# FPGA_POWER.net
KiCad netlist of a schematic drawn in Altium Designer
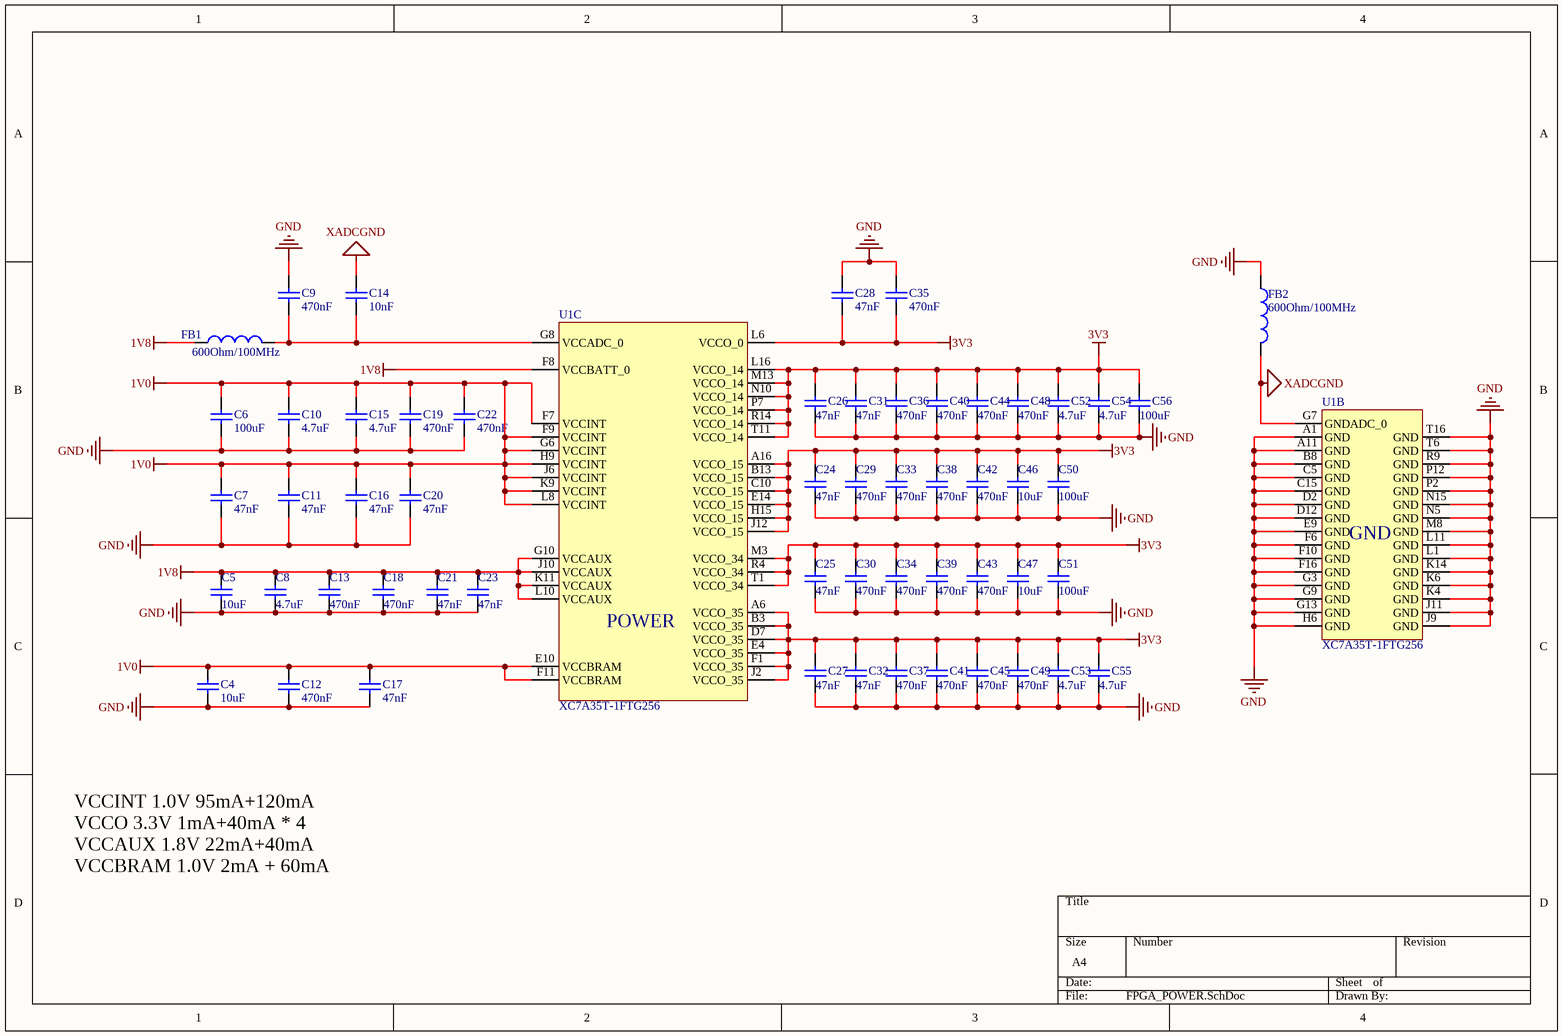
[diagram p0: FPGA_POWER.SchDoc]

(export (version "E")
  (design (tool "Eeschema 10.0.6"))
  (components
    (comp (ref "C4")
      (value "10uF")
      (footprint "0402")
      (description "贴片电容")
      (fields (field (name "Comment") "Cap") (field (name "PUBLISHER") "Altium Limited"))
      (libsource (lib "Sparks") (part "Cap"))
    )
    (comp (ref "C5")
      (value "10uF")
      (footprint "0402")
      (description "贴片电容")
      (fields (field (name "Comment") "Cap") (field (name "PUBLISHER") "Altium Limited"))
      (libsource (lib "Sparks") (part "Cap"))
    )
    (comp (ref "C6")
      (value "100uF")
      (footprint "1206")
      (description "贴片电容")
      (fields (field (name "Comment") "Cap") (field (name "PUBLISHER") "Altium Limited"))
      (libsource (lib "Sparks") (part "Cap"))
    )
    (comp (ref "C7")
      (value "47nF")
      (footprint "0402")
      (description "贴片电容")
      (fields (field (name "Comment") "Cap") (field (name "PUBLISHER") "Altium Limited"))
      (libsource (lib "Sparks") (part "Cap"))
    )
    (comp (ref "C8")
      (value "4.7uF")
      (footprint "0402")
      (description "贴片电容")
      (fields (field (name "Comment") "Cap") (field (name "PUBLISHER") "Altium Limited"))
      (libsource (lib "Sparks") (part "Cap"))
    )
    (comp (ref "C9")
      (value "470nF")
      (footprint "0402")
      (description "贴片电容")
      (fields (field (name "Comment") "Cap") (field (name "PUBLISHER") "Altium Limited"))
      (libsource (lib "Sparks") (part "Cap"))
    )
    (comp (ref "C10")
      (value "4.7uF")
      (footprint "0402")
      (description "贴片电容")
      (fields (field (name "Comment") "Cap") (field (name "PUBLISHER") "Altium Limited"))
      (libsource (lib "Sparks") (part "Cap"))
    )
    (comp (ref "C11")
      (value "47nF")
      (footprint "0402")
      (description "贴片电容")
      (fields (field (name "Comment") "Cap") (field (name "PUBLISHER") "Altium Limited"))
      (libsource (lib "Sparks") (part "Cap"))
    )
    (comp (ref "C12")
      (value "470nF")
      (footprint "0402")
      (description "贴片电容")
      (fields (field (name "Comment") "Cap") (field (name "PUBLISHER") "Altium Limited"))
      (libsource (lib "Sparks") (part "Cap"))
    )
    (comp (ref "C13")
      (value "470nF")
      (footprint "0402")
      (description "贴片电容")
      (fields (field (name "Comment") "Cap") (field (name "PUBLISHER") "Altium Limited"))
      (libsource (lib "Sparks") (part "Cap"))
    )
    (comp (ref "C14")
      (value "10nF")
      (footprint "0402")
      (description "贴片电容")
      (fields (field (name "Comment") "Cap") (field (name "PUBLISHER") "Altium Limited"))
      (libsource (lib "Sparks") (part "Cap"))
    )
    (comp (ref "C15")
      (value "4.7uF")
      (footprint "0402")
      (description "贴片电容")
      (fields (field (name "Comment") "Cap") (field (name "PUBLISHER") "Altium Limited"))
      (libsource (lib "Sparks") (part "Cap"))
    )
    (comp (ref "C16")
      (value "47nF")
      (footprint "0402")
      (description "贴片电容")
      (fields (field (name "Comment") "Cap") (field (name "PUBLISHER") "Altium Limited"))
      (libsource (lib "Sparks") (part "Cap"))
    )
    (comp (ref "C17")
      (value "47nF")
      (footprint "0402")
      (description "贴片电容")
      (fields (field (name "Comment") "Cap") (field (name "PUBLISHER") "Altium Limited"))
      (libsource (lib "Sparks") (part "Cap"))
    )
    (comp (ref "C18")
      (value "470nF")
      (footprint "0402")
      (description "贴片电容")
      (fields (field (name "Comment") "Cap") (field (name "PUBLISHER") "Altium Limited"))
      (libsource (lib "Sparks") (part "Cap"))
    )
    (comp (ref "C19")
      (value "470nF")
      (footprint "0402")
      (description "贴片电容")
      (fields (field (name "Comment") "Cap") (field (name "PUBLISHER") "Altium Limited"))
      (libsource (lib "Sparks") (part "Cap"))
    )
    (comp (ref "C20")
      (value "47nF")
      (footprint "0402")
      (description "贴片电容")
      (fields (field (name "Comment") "Cap") (field (name "PUBLISHER") "Altium Limited"))
      (libsource (lib "Sparks") (part "Cap"))
    )
    (comp (ref "C21")
      (value "47nF")
      (footprint "0402")
      (description "贴片电容")
      (fields (field (name "Comment") "Cap") (field (name "PUBLISHER") "Altium Limited"))
      (libsource (lib "Sparks") (part "Cap"))
    )
    (comp (ref "C22")
      (value "470nF")
      (footprint "0402")
      (description "贴片电容")
      (fields (field (name "Comment") "Cap") (field (name "PUBLISHER") "Altium Limited"))
      (libsource (lib "Sparks") (part "Cap"))
    )
    (comp (ref "C23")
      (value "47nF")
      (footprint "0402")
      (description "贴片电容")
      (fields (field (name "Comment") "Cap") (field (name "PUBLISHER") "Altium Limited"))
      (libsource (lib "Sparks") (part "Cap"))
    )
    (comp (ref "C24")
      (value "47nF")
      (footprint "0402")
      (description "贴片电容")
      (fields (field (name "Comment") "Cap") (field (name "PUBLISHER") "Altium Limited"))
      (libsource (lib "Sparks") (part "Cap"))
    )
    (comp (ref "C25")
      (value "47nF")
      (footprint "0402")
      (description "贴片电容")
      (fields (field (name "Comment") "Cap") (field (name "PUBLISHER") "Altium Limited"))
      (libsource (lib "Sparks") (part "Cap"))
    )
    (comp (ref "C26")
      (value "47nF")
      (footprint "0402")
      (description "贴片电容")
      (fields (field (name "Comment") "Cap") (field (name "PUBLISHER") "Altium Limited"))
      (libsource (lib "Sparks") (part "Cap"))
    )
    (comp (ref "C27")
      (value "47nF")
      (footprint "0402")
      (description "贴片电容")
      (fields (field (name "Comment") "Cap") (field (name "PUBLISHER") "Altium Limited"))
      (libsource (lib "Sparks") (part "Cap"))
    )
    (comp (ref "C28")
      (value "47nF")
      (footprint "0402")
      (description "贴片电容")
      (fields (field (name "Comment") "Cap") (field (name "PUBLISHER") "Altium Limited"))
      (libsource (lib "Sparks") (part "Cap"))
    )
    (comp (ref "C29")
      (value "470nF")
      (footprint "0402")
      (description "贴片电容")
      (fields (field (name "Comment") "Cap") (field (name "PUBLISHER") "Altium Limited"))
      (libsource (lib "Sparks") (part "Cap"))
    )
    (comp (ref "C30")
      (value "470nF")
      (footprint "0402")
      (description "贴片电容")
      (fields (field (name "Comment") "Cap") (field (name "PUBLISHER") "Altium Limited"))
      (libsource (lib "Sparks") (part "Cap"))
    )
    (comp (ref "C31")
      (value "47nF")
      (footprint "0402")
      (description "贴片电容")
      (fields (field (name "Comment") "Cap") (field (name "PUBLISHER") "Altium Limited"))
      (libsource (lib "Sparks") (part "Cap"))
    )
    (comp (ref "C32")
      (value "47nF")
      (footprint "0402")
      (description "贴片电容")
      (fields (field (name "Comment") "Cap") (field (name "PUBLISHER") "Altium Limited"))
      (libsource (lib "Sparks") (part "Cap"))
    )
    (comp (ref "C33")
      (value "470nF")
      (footprint "0402")
      (description "贴片电容")
      (fields (field (name "Comment") "Cap") (field (name "PUBLISHER") "Altium Limited"))
      (libsource (lib "Sparks") (part "Cap"))
    )
    (comp (ref "C34")
      (value "470nF")
      (footprint "0402")
      (description "贴片电容")
      (fields (field (name "Comment") "Cap") (field (name "PUBLISHER") "Altium Limited"))
      (libsource (lib "Sparks") (part "Cap"))
    )
    (comp (ref "C35")
      (value "470nF")
      (footprint "0402")
      (description "贴片电容")
      (fields (field (name "Comment") "Cap") (field (name "PUBLISHER") "Altium Limited"))
      (libsource (lib "Sparks") (part "Cap"))
    )
    (comp (ref "C36")
      (value "470nF")
      (footprint "0402")
      (description "贴片电容")
      (fields (field (name "Comment") "Cap") (field (name "PUBLISHER") "Altium Limited"))
      (libsource (lib "Sparks") (part "Cap"))
    )
    (comp (ref "C37")
      (value "470nF")
      (footprint "0402")
      (description "贴片电容")
      (fields (field (name "Comment") "Cap") (field (name "PUBLISHER") "Altium Limited"))
      (libsource (lib "Sparks") (part "Cap"))
    )
    (comp (ref "C38")
      (value "470nF")
      (footprint "0402")
      (description "贴片电容")
      (fields (field (name "Comment") "Cap") (field (name "PUBLISHER") "Altium Limited"))
      (libsource (lib "Sparks") (part "Cap"))
    )
    (comp (ref "C39")
      (value "470nF")
      (footprint "0402")
      (description "贴片电容")
      (fields (field (name "Comment") "Cap") (field (name "PUBLISHER") "Altium Limited"))
      (libsource (lib "Sparks") (part "Cap"))
    )
    (comp (ref "C40")
      (value "470nF")
      (footprint "0402")
      (description "贴片电容")
      (fields (field (name "Comment") "Cap") (field (name "PUBLISHER") "Altium Limited"))
      (libsource (lib "Sparks") (part "Cap"))
    )
    (comp (ref "C41")
      (value "470nF")
      (footprint "0402")
      (description "贴片电容")
      (fields (field (name "Comment") "Cap") (field (name "PUBLISHER") "Altium Limited"))
      (libsource (lib "Sparks") (part "Cap"))
    )
    (comp (ref "C42")
      (value "470nF")
      (footprint "0402")
      (description "贴片电容")
      (fields (field (name "Comment") "Cap") (field (name "PUBLISHER") "Altium Limited"))
      (libsource (lib "Sparks") (part "Cap"))
    )
    (comp (ref "C43")
      (value "470nF")
      (footprint "0402")
      (description "贴片电容")
      (fields (field (name "Comment") "Cap") (field (name "PUBLISHER") "Altium Limited"))
      (libsource (lib "Sparks") (part "Cap"))
    )
    (comp (ref "C44")
      (value "470nF")
      (footprint "0402")
      (description "贴片电容")
      (fields (field (name "Comment") "Cap") (field (name "PUBLISHER") "Altium Limited"))
      (libsource (lib "Sparks") (part "Cap"))
    )
    (comp (ref "C45")
      (value "470nF")
      (footprint "0402")
      (description "贴片电容")
      (fields (field (name "Comment") "Cap") (field (name "PUBLISHER") "Altium Limited"))
      (libsource (lib "Sparks") (part "Cap"))
    )
    (comp (ref "C46")
      (value "10uF")
      (footprint "0402")
      (description "贴片电容")
      (fields (field (name "Comment") "Cap") (field (name "PUBLISHER") "Altium Limited"))
      (libsource (lib "Sparks") (part "Cap"))
    )
    (comp (ref "C47")
      (value "10uF")
      (footprint "0402")
      (description "贴片电容")
      (fields (field (name "Comment") "Cap") (field (name "PUBLISHER") "Altium Limited"))
      (libsource (lib "Sparks") (part "Cap"))
    )
    (comp (ref "C48")
      (value "470nF")
      (footprint "0402")
      (description "贴片电容")
      (fields (field (name "Comment") "Cap") (field (name "PUBLISHER") "Altium Limited"))
      (libsource (lib "Sparks") (part "Cap"))
    )
    (comp (ref "C49")
      (value "470nF")
      (footprint "0402")
      (description "贴片电容")
      (fields (field (name "Comment") "Cap") (field (name "PUBLISHER") "Altium Limited"))
      (libsource (lib "Sparks") (part "Cap"))
    )
    (comp (ref "C50")
      (value "100uF")
      (footprint "1206")
      (description "贴片电容")
      (fields (field (name "Comment") "Cap") (field (name "PUBLISHER") "Altium Limited"))
      (libsource (lib "Sparks") (part "Cap"))
    )
    (comp (ref "C51")
      (value "100uF")
      (footprint "1206")
      (description "贴片电容")
      (fields (field (name "Comment") "Cap") (field (name "PUBLISHER") "Altium Limited"))
      (libsource (lib "Sparks") (part "Cap"))
    )
    (comp (ref "C52")
      (value "4.7uF")
      (footprint "0402")
      (description "贴片电容")
      (fields (field (name "Comment") "Cap") (field (name "PUBLISHER") "Altium Limited"))
      (libsource (lib "Sparks") (part "Cap"))
    )
    (comp (ref "C53")
      (value "4.7uF")
      (footprint "0402")
      (description "贴片电容")
      (fields (field (name "Comment") "Cap") (field (name "PUBLISHER") "Altium Limited"))
      (libsource (lib "Sparks") (part "Cap"))
    )
    (comp (ref "C54")
      (value "4.7uF")
      (footprint "0402")
      (description "贴片电容")
      (fields (field (name "Comment") "Cap") (field (name "PUBLISHER") "Altium Limited"))
      (libsource (lib "Sparks") (part "Cap"))
    )
    (comp (ref "C55")
      (value "4.7uF")
      (footprint "0402")
      (description "贴片电容")
      (fields (field (name "Comment") "Cap") (field (name "PUBLISHER") "Altium Limited"))
      (libsource (lib "Sparks") (part "Cap"))
    )
    (comp (ref "C56")
      (value "100uF")
      (footprint "1206")
      (description "贴片电容")
      (fields (field (name "Comment") "Cap") (field (name "PUBLISHER") "Altium Limited"))
      (libsource (lib "Sparks") (part "Cap"))
    )
    (comp (ref "FB1")
      (value "600Ohm/100MHz")
      (footprint "0402")
      (description "Inductor")
      (fields (field (name "PUBLISHER") "Altium Limited"))
      (libsource (lib "Miscellaneous Devices") (part "Inductor"))
    )
    (comp (ref "FB2")
      (value "600Ohm/100MHz")
      (footprint "0402")
      (description "Inductor")
      (fields (field (name "PUBLISHER") "Altium Limited"))
      (libsource (lib "Miscellaneous Devices") (part "Inductor"))
    )
    (comp (ref "U1")
      (value "XC7A35T-1FTG256")
      (footprint "BGA100P9X9-81A")
      (libsource (lib "Schlib") (part "XC7A35T-1FTG256"))
    )
  )
  (nets
    (net (code "1") (name "1V0") (class "Default")
      (node (ref "C10") (pin "1") (pinfunction "1_1") (pintype "passive"))
      (node (ref "C11") (pin "1") (pinfunction "1_1") (pintype "passive"))
      (node (ref "C12") (pin "1") (pinfunction "1_1") (pintype "passive"))
      (node (ref "C15") (pin "1") (pinfunction "1_1") (pintype "passive"))
      (node (ref "C16") (pin "1") (pinfunction "1_1") (pintype "passive"))
      (node (ref "C17") (pin "1") (pinfunction "1_1") (pintype "passive"))
      (node (ref "C19") (pin "1") (pinfunction "1_1") (pintype "passive"))
      (node (ref "C20") (pin "1") (pinfunction "1_1") (pintype "passive"))
      (node (ref "C22") (pin "1") (pinfunction "1_1") (pintype "passive"))
      (node (ref "C4") (pin "1") (pinfunction "1_1") (pintype "passive"))
      (node (ref "C6") (pin "1") (pinfunction "1_1") (pintype "passive"))
      (node (ref "C7") (pin "1") (pinfunction "1_1") (pintype "passive"))
      (node (ref "U1") (pin "E10") (pinfunction "VCCBRAM_E10") (pintype "passive"))
      (node (ref "U1") (pin "F11") (pinfunction "VCCBRAM_F11") (pintype "passive"))
      (node (ref "U1") (pin "F7") (pinfunction "VCCINT_F7") (pintype "passive"))
      (node (ref "U1") (pin "F9") (pinfunction "VCCINT_F9") (pintype "passive"))
      (node (ref "U1") (pin "G6") (pinfunction "VCCINT_G6") (pintype "passive"))
      (node (ref "U1") (pin "H9") (pinfunction "VCCINT_H9") (pintype "passive"))
      (node (ref "U1") (pin "J6") (pinfunction "VCCINT_J6") (pintype "passive"))
      (node (ref "U1") (pin "K9") (pinfunction "VCCINT_K9") (pintype "passive"))
      (node (ref "U1") (pin "L8") (pinfunction "VCCINT_L8") (pintype "passive"))
    )
    (net (code "2") (name "1V8") (class "Default")
      (node (ref "C13") (pin "1") (pinfunction "1_1") (pintype "passive"))
      (node (ref "C18") (pin "1") (pinfunction "1_1") (pintype "passive"))
      (node (ref "C21") (pin "1") (pinfunction "1_1") (pintype "passive"))
      (node (ref "C23") (pin "1") (pinfunction "1_1") (pintype "passive"))
      (node (ref "C5") (pin "1") (pinfunction "1_1") (pintype "passive"))
      (node (ref "C8") (pin "1") (pinfunction "1_1") (pintype "passive"))
      (node (ref "FB1") (pin "1") (pinfunction "1_1") (pintype "passive"))
      (node (ref "U1") (pin "F8") (pinfunction "VCCBATT_0_F8") (pintype "passive"))
      (node (ref "U1") (pin "G10") (pinfunction "VCCAUX_G10") (pintype "passive"))
      (node (ref "U1") (pin "J10") (pinfunction "VCCAUX_J10") (pintype "passive"))
      (node (ref "U1") (pin "K11") (pinfunction "VCCAUX_K11") (pintype "passive"))
      (node (ref "U1") (pin "L10") (pinfunction "VCCAUX_L10") (pintype "passive"))
    )
    (net (code "3") (name "3V3") (class "Default")
      (node (ref "C24") (pin "1") (pinfunction "1_1") (pintype "passive"))
      (node (ref "C25") (pin "1") (pinfunction "1_1") (pintype "passive"))
      (node (ref "C26") (pin "1") (pinfunction "1_1") (pintype "passive"))
      (node (ref "C27") (pin "1") (pinfunction "1_1") (pintype "passive"))
      (node (ref "C28") (pin "2") (pinfunction "2_2") (pintype "passive"))
      (node (ref "C29") (pin "1") (pinfunction "1_1") (pintype "passive"))
      (node (ref "C30") (pin "1") (pinfunction "1_1") (pintype "passive"))
      (node (ref "C31") (pin "1") (pinfunction "1_1") (pintype "passive"))
      (node (ref "C32") (pin "1") (pinfunction "1_1") (pintype "passive"))
      (node (ref "C33") (pin "1") (pinfunction "1_1") (pintype "passive"))
      (node (ref "C34") (pin "1") (pinfunction "1_1") (pintype "passive"))
      (node (ref "C35") (pin "2") (pinfunction "2_2") (pintype "passive"))
      (node (ref "C36") (pin "1") (pinfunction "1_1") (pintype "passive"))
      (node (ref "C37") (pin "1") (pinfunction "1_1") (pintype "passive"))
      (node (ref "C38") (pin "1") (pinfunction "1_1") (pintype "passive"))
      (node (ref "C39") (pin "1") (pinfunction "1_1") (pintype "passive"))
      (node (ref "C40") (pin "1") (pinfunction "1_1") (pintype "passive"))
      (node (ref "C41") (pin "1") (pinfunction "1_1") (pintype "passive"))
      (node (ref "C42") (pin "1") (pinfunction "1_1") (pintype "passive"))
      (node (ref "C43") (pin "1") (pinfunction "1_1") (pintype "passive"))
      (node (ref "C44") (pin "1") (pinfunction "1_1") (pintype "passive"))
      (node (ref "C45") (pin "1") (pinfunction "1_1") (pintype "passive"))
      (node (ref "C46") (pin "1") (pinfunction "1_1") (pintype "passive"))
      (node (ref "C47") (pin "1") (pinfunction "1_1") (pintype "passive"))
      (node (ref "C48") (pin "1") (pinfunction "1_1") (pintype "passive"))
      (node (ref "C49") (pin "1") (pinfunction "1_1") (pintype "passive"))
      (node (ref "C50") (pin "1") (pinfunction "1_1") (pintype "passive"))
      (node (ref "C51") (pin "1") (pinfunction "1_1") (pintype "passive"))
      (node (ref "C52") (pin "1") (pinfunction "1_1") (pintype "passive"))
      (node (ref "C53") (pin "1") (pinfunction "1_1") (pintype "passive"))
      (node (ref "C54") (pin "1") (pinfunction "1_1") (pintype "passive"))
      (node (ref "C55") (pin "1") (pinfunction "1_1") (pintype "passive"))
      (node (ref "C56") (pin "1") (pinfunction "1_1") (pintype "passive"))
      (node (ref "U1") (pin "A16") (pinfunction "VCCO_15_A16") (pintype "passive"))
      (node (ref "U1") (pin "A6") (pinfunction "VCCO_35_A6") (pintype "passive"))
      (node (ref "U1") (pin "B13") (pinfunction "VCCO_15_B13") (pintype "passive"))
      (node (ref "U1") (pin "B3") (pinfunction "VCCO_35_B3") (pintype "passive"))
      (node (ref "U1") (pin "C10") (pinfunction "VCCO_15_C10") (pintype "passive"))
      (node (ref "U1") (pin "D7") (pinfunction "VCCO_35_D7") (pintype "passive"))
      (node (ref "U1") (pin "E14") (pinfunction "VCCO_15_E14") (pintype "passive"))
      (node (ref "U1") (pin "E4") (pinfunction "VCCO_35_E4") (pintype "passive"))
      (node (ref "U1") (pin "F1") (pinfunction "VCCO_35_F1") (pintype "passive"))
      (node (ref "U1") (pin "H15") (pinfunction "VCCO_15_H15") (pintype "passive"))
      (node (ref "U1") (pin "J12") (pinfunction "VCCO_15_J12") (pintype "passive"))
      (node (ref "U1") (pin "J2") (pinfunction "VCCO_35_J2") (pintype "passive"))
      (node (ref "U1") (pin "L16") (pinfunction "VCCO_14_L16") (pintype "passive"))
      (node (ref "U1") (pin "L6") (pinfunction "VCCO_0_L6") (pintype "passive"))
      (node (ref "U1") (pin "M13") (pinfunction "VCCO_14_M13") (pintype "passive"))
      (node (ref "U1") (pin "M3") (pinfunction "VCCO_34_M3") (pintype "passive"))
      (node (ref "U1") (pin "N10") (pinfunction "VCCO_14_N10") (pintype "passive"))
      (node (ref "U1") (pin "P7") (pinfunction "VCCO_14_P7") (pintype "passive"))
      (node (ref "U1") (pin "R14") (pinfunction "VCCO_14_R14") (pintype "passive"))
      (node (ref "U1") (pin "R4") (pinfunction "VCCO_34_R4") (pintype "passive"))
      (node (ref "U1") (pin "T1") (pinfunction "VCCO_34_T1") (pintype "passive"))
      (node (ref "U1") (pin "T11") (pinfunction "VCCO_14_T11") (pintype "passive"))
    )
    (net (code "4") (name "GND") (class "Default")
      (node (ref "C10") (pin "2") (pinfunction "2_2") (pintype "passive"))
      (node (ref "C11") (pin "2") (pinfunction "2_2") (pintype "passive"))
      (node (ref "C12") (pin "2") (pinfunction "2_2") (pintype "passive"))
      (node (ref "C13") (pin "2") (pinfunction "2_2") (pintype "passive"))
      (node (ref "C15") (pin "2") (pinfunction "2_2") (pintype "passive"))
      (node (ref "C16") (pin "2") (pinfunction "2_2") (pintype "passive"))
      (node (ref "C17") (pin "2") (pinfunction "2_2") (pintype "passive"))
      (node (ref "C18") (pin "2") (pinfunction "2_2") (pintype "passive"))
      (node (ref "C19") (pin "2") (pinfunction "2_2") (pintype "passive"))
      (node (ref "C20") (pin "2") (pinfunction "2_2") (pintype "passive"))
      (node (ref "C21") (pin "2") (pinfunction "2_2") (pintype "passive"))
      (node (ref "C22") (pin "2") (pinfunction "2_2") (pintype "passive"))
      (node (ref "C23") (pin "2") (pinfunction "2_2") (pintype "passive"))
      (node (ref "C24") (pin "2") (pinfunction "2_2") (pintype "passive"))
      (node (ref "C25") (pin "2") (pinfunction "2_2") (pintype "passive"))
      (node (ref "C26") (pin "2") (pinfunction "2_2") (pintype "passive"))
      (node (ref "C27") (pin "2") (pinfunction "2_2") (pintype "passive"))
      (node (ref "C28") (pin "1") (pinfunction "1_1") (pintype "passive"))
      (node (ref "C29") (pin "2") (pinfunction "2_2") (pintype "passive"))
      (node (ref "C30") (pin "2") (pinfunction "2_2") (pintype "passive"))
      (node (ref "C31") (pin "2") (pinfunction "2_2") (pintype "passive"))
      (node (ref "C32") (pin "2") (pinfunction "2_2") (pintype "passive"))
      (node (ref "C33") (pin "2") (pinfunction "2_2") (pintype "passive"))
      (node (ref "C34") (pin "2") (pinfunction "2_2") (pintype "passive"))
      (node (ref "C35") (pin "1") (pinfunction "1_1") (pintype "passive"))
      (node (ref "C36") (pin "2") (pinfunction "2_2") (pintype "passive"))
      (node (ref "C37") (pin "2") (pinfunction "2_2") (pintype "passive"))
      (node (ref "C38") (pin "2") (pinfunction "2_2") (pintype "passive"))
      (node (ref "C39") (pin "2") (pinfunction "2_2") (pintype "passive"))
      (node (ref "C4") (pin "2") (pinfunction "2_2") (pintype "passive"))
      (node (ref "C40") (pin "2") (pinfunction "2_2") (pintype "passive"))
      (node (ref "C41") (pin "2") (pinfunction "2_2") (pintype "passive"))
      (node (ref "C42") (pin "2") (pinfunction "2_2") (pintype "passive"))
      (node (ref "C43") (pin "2") (pinfunction "2_2") (pintype "passive"))
      (node (ref "C44") (pin "2") (pinfunction "2_2") (pintype "passive"))
      (node (ref "C45") (pin "2") (pinfunction "2_2") (pintype "passive"))
      (node (ref "C46") (pin "2") (pinfunction "2_2") (pintype "passive"))
      (node (ref "C47") (pin "2") (pinfunction "2_2") (pintype "passive"))
      (node (ref "C48") (pin "2") (pinfunction "2_2") (pintype "passive"))
      (node (ref "C49") (pin "2") (pinfunction "2_2") (pintype "passive"))
      (node (ref "C5") (pin "2") (pinfunction "2_2") (pintype "passive"))
      (node (ref "C50") (pin "2") (pinfunction "2_2") (pintype "passive"))
      (node (ref "C51") (pin "2") (pinfunction "2_2") (pintype "passive"))
      (node (ref "C52") (pin "2") (pinfunction "2_2") (pintype "passive"))
      (node (ref "C53") (pin "2") (pinfunction "2_2") (pintype "passive"))
      (node (ref "C54") (pin "2") (pinfunction "2_2") (pintype "passive"))
      (node (ref "C55") (pin "2") (pinfunction "2_2") (pintype "passive"))
      (node (ref "C56") (pin "2") (pinfunction "2_2") (pintype "passive"))
      (node (ref "C6") (pin "2") (pinfunction "2_2") (pintype "passive"))
      (node (ref "C7") (pin "2") (pinfunction "2_2") (pintype "passive"))
      (node (ref "C8") (pin "2") (pinfunction "2_2") (pintype "passive"))
      (node (ref "C9") (pin "1") (pinfunction "1_1") (pintype "passive"))
      (node (ref "FB2") (pin "1") (pinfunction "1_1") (pintype "passive"))
      (node (ref "U1") (pin "A1") (pinfunction "GND_A1") (pintype "passive"))
      (node (ref "U1") (pin "A11") (pinfunction "GND_A11") (pintype "passive"))
      (node (ref "U1") (pin "B8") (pinfunction "GND_B8") (pintype "passive"))
      (node (ref "U1") (pin "C15") (pinfunction "GND_C15") (pintype "passive"))
      (node (ref "U1") (pin "C5") (pinfunction "GND_C5") (pintype "passive"))
      (node (ref "U1") (pin "D12") (pinfunction "GND_D12") (pintype "passive"))
      (node (ref "U1") (pin "D2") (pinfunction "GND_D2") (pintype "passive"))
      (node (ref "U1") (pin "E9") (pinfunction "GND_E9") (pintype "passive"))
      (node (ref "U1") (pin "F10") (pinfunction "GND_F10") (pintype "passive"))
      (node (ref "U1") (pin "F16") (pinfunction "GND_F16") (pintype "passive"))
      (node (ref "U1") (pin "F6") (pinfunction "GND_F6") (pintype "passive"))
      (node (ref "U1") (pin "G13") (pinfunction "GND_G13") (pintype "passive"))
      (node (ref "U1") (pin "G3") (pinfunction "GND_G3") (pintype "passive"))
      (node (ref "U1") (pin "G9") (pinfunction "GND_G9") (pintype "passive"))
      (node (ref "U1") (pin "H6") (pinfunction "GND_H6") (pintype "passive"))
      (node (ref "U1") (pin "J11") (pinfunction "GND_J11") (pintype "passive"))
      (node (ref "U1") (pin "J9") (pinfunction "GND_J9") (pintype "passive"))
      (node (ref "U1") (pin "K14") (pinfunction "GND_K14") (pintype "passive"))
      (node (ref "U1") (pin "K4") (pinfunction "GND_K4") (pintype "passive"))
      (node (ref "U1") (pin "K6") (pinfunction "GND_K6") (pintype "passive"))
      (node (ref "U1") (pin "L1") (pinfunction "GND_L1") (pintype "passive"))
      (node (ref "U1") (pin "L11") (pinfunction "GND_L11") (pintype "passive"))
      (node (ref "U1") (pin "M8") (pinfunction "GND_M8") (pintype "passive"))
      (node (ref "U1") (pin "N15") (pinfunction "GND_N15") (pintype "passive"))
      (node (ref "U1") (pin "N5") (pinfunction "GND_N5") (pintype "passive"))
      (node (ref "U1") (pin "P12") (pinfunction "GND_P12") (pintype "passive"))
      (node (ref "U1") (pin "P2") (pinfunction "GND_P2") (pintype "passive"))
      (node (ref "U1") (pin "R9") (pinfunction "GND_R9") (pintype "passive"))
      (node (ref "U1") (pin "T16") (pinfunction "GND_T16") (pintype "passive"))
      (node (ref "U1") (pin "T6") (pinfunction "GND_T6") (pintype "passive"))
    )
    (net (code "5") (name "Net-(U1C-VCCADC_0)") (class "Default")
      (node (ref "C14") (pin "1") (pinfunction "1_1") (pintype "passive"))
      (node (ref "C9") (pin "2") (pinfunction "2_2") (pintype "passive"))
      (node (ref "FB1") (pin "2") (pinfunction "2_2") (pintype "passive"))
      (node (ref "U1") (pin "G8") (pinfunction "VCCADC_0_G8") (pintype "passive"))
    )
    (net (code "6") (name "XADCGND") (class "Default")
      (node (ref "C14") (pin "2") (pinfunction "2_2") (pintype "passive"))
      (node (ref "FB2") (pin "2") (pinfunction "2_2") (pintype "passive"))
      (node (ref "U1") (pin "G7") (pinfunction "GNDADC_0_G7") (pintype "passive"))
    )
  )
)
